# TPS22680.net
KiCad netlist of a schematic drawn in EAGLE
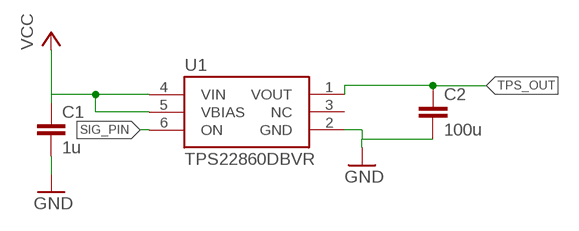
[diagram p0: schematic, sheet 1]

(export (version "E")
  (design (tool "Eeschema 10.0.6"))
  (components
    (comp (ref "C1")
      (value "1u")
      (footprint "eagle-import:C0603")
      (libsource (lib "eagle-import") (part "C-EUC0603"))
    )
    (comp (ref "C2")
      (value "100u")
      (footprint "eagle-import:C0603")
      (libsource (lib "eagle-import") (part "C-EUC0603"))
    )
    (comp (ref "U1")
      (value "TPS22860DBVR")
      (footprint "eagle-import:R-PDSO-G6")
      (libsource (lib "eagle-import") (part "TPS22860DBVR"))
    )
  )
  (nets
    (net (code "1") (name "GND") (class "Default")
      (node (ref "C1") (pin "2") (pinfunction "2_2") (pintype "passive"))
      (node (ref "C2") (pin "2") (pinfunction "2_2") (pintype "passive"))
      (node (ref "U1") (pin "2") (pinfunction "GND_2") (pintype "power_in"))
    )
    (net (code "2") (name "SIG_PIN") (class "Default")
      (node (ref "U1") (pin "6") (pinfunction "ON_6") (pintype "input"))
    )
    (net (code "3") (name "TPS_OUT") (class "Default")
      (node (ref "C2") (pin "1") (pinfunction "1_1") (pintype "passive"))
      (node (ref "U1") (pin "1") (pinfunction "VOUT_1") (pintype "power_in"))
    )
    (net (code "4") (name "VCC") (class "Default")
      (node (ref "C1") (pin "1") (pinfunction "1_1") (pintype "passive"))
      (node (ref "U1") (pin "4") (pinfunction "VIN_4") (pintype "power_in"))
      (node (ref "U1") (pin "5") (pinfunction "VBIAS_5") (pintype "power_in"))
    )
    (net (code "5") (name "unconnected-(U1-NC-Pad3)") (class "Default")
      (node (ref "U1") (pin "3") (pinfunction "NC_3") (pintype "no_connect"))
    )
  )
)
